# Real_Time_Clock.net
KiCad netlist of a schematic drawn in Altium Designer
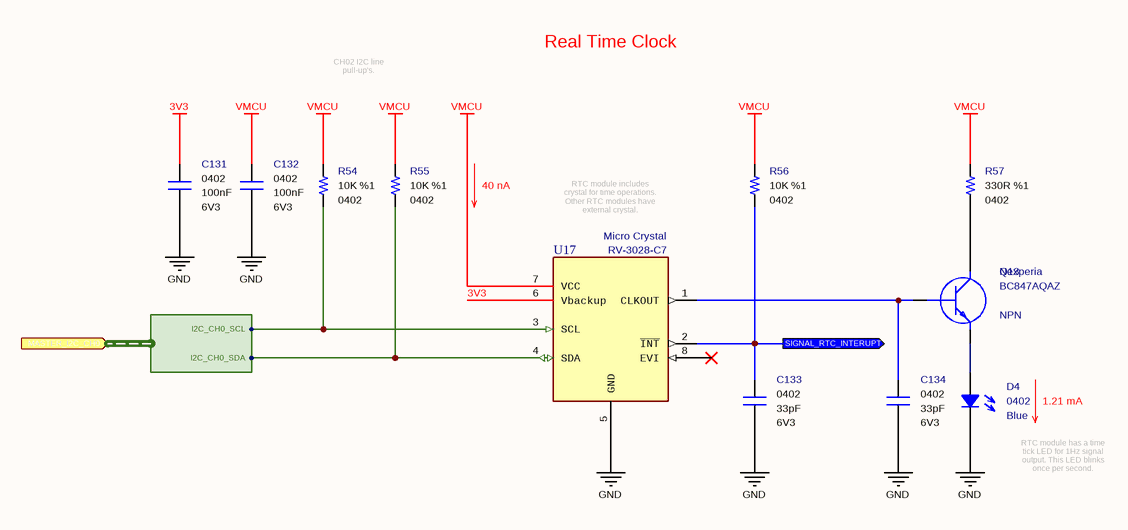
[diagram p0: Real Time Clock.SchDoc]

(export (version "E")
  (design (tool "Eeschema 10.0.6"))
  (components
    (comp (ref "C131")
      (value "100nF")
      (footprint "CAPACITOR_0402")
      (description "Capacitor - 100nF [0402-6V3] (Ceramic)")
      (fields
        (field (name "TOLERANCE") "%10")
        (field (name "CASE") "0402")
        (field (name "VOLTAGE") "6V3")
        (field (name "MANUFACTURER PART NUMBER") "04026D104KAT4A")
      )
      (libsource (lib "Ovoo_Library") (part "Capacitor - 100nF [0402-6V3]"))
    )
    (comp (ref "C132")
      (value "100nF")
      (footprint "CAPACITOR_0402")
      (description "Capacitor - 100nF [0402-6V3] (Ceramic)")
      (fields
        (field (name "TOLERANCE") "%10")
        (field (name "CASE") "0402")
        (field (name "VOLTAGE") "6V3")
        (field (name "MANUFACTURER PART NUMBER") "04026D104KAT4A")
      )
      (libsource (lib "Ovoo_Library") (part "Capacitor - 100nF [0402-6V3]"))
    )
    (comp (ref "C133")
      (value "33pF")
      (footprint "CAPACITOR_0402")
      (description "Capacitor - 33pF [0402] (Ceramic)")
      (fields
        (field (name "CASE") "0402")
        (field (name "TOLERANCE") "10%")
        (field (name "VOLTAGE") "6V3")
        (field (name "MANUFACTURER PART NUMBER") "C0402C330J9RACAUTO")
      )
      (libsource (lib "Ovoo_Library") (part "Capacitor - 33pF [0402-6V3]"))
    )
    (comp (ref "C134")
      (value "33pF")
      (footprint "CAPACITOR_0402")
      (description "Capacitor - 33pF [0402] (Ceramic)")
      (fields
        (field (name "CASE") "0402")
        (field (name "TOLERANCE") "10%")
        (field (name "VOLTAGE") "6V3")
        (field (name "MANUFACTURER PART NUMBER") "C0402C330J9RACAUTO")
      )
      (libsource (lib "Ovoo_Library") (part "Capacitor - 33pF [0402-6V3]"))
    )
    (comp (ref "D4")
      (value "SMD LED (Blue)")
      (footprint "LED_0402")
      (description "Standard LEDs - SMD PICOLEDTM;BLUE LED; 25M @ 5MA")
      (fields
        (field (name "CASE") "0402")
        (field (name "COLOR") "Blue")
        (field (name "MANUFACTURER PART NUMBER") "SMLP13BC8TT86")
        (field (name "MOUSER PART NUMBER") "755-SMLP13BC8TT86")
      )
      (libsource (lib "Ovoo_Library") (part "Diode - LED (0402-Blue)"))
    )
    (comp (ref "Q13")
      (value "Bipolar NPN Transistors")
      (footprint "SOT1215")
      (description "Bipolar Transistors - BJT BC847AQA/DFN1010D-3/REEL 7\" Q2")
      (fields
        (field (name "POLARITY") "NPN")
        (field (name "MOUSER PART NUMBER") "771-BC847AQAZ")
        (field (name "MANUFACTURER NAME") "Nexperia")
        (field (name "MANUFACTURER PART NUMBER") "BC847AQAZ")
      )
      (libsource (lib "Ovoo_Library") (part "Transistor - BC847"))
    )
    (comp (ref "R54")
      (value "10K")
      (footprint "RESISTOR_0402")
      (description "Thick Film Resistors - SMD 1/16 W 10 Kohms 1%")
      (fields
        (field (name "TOLERANCE") "%1")
        (field (name "CASE") "0402")
        (field (name "MANUFACTURER PART NUMBER") "CRCW040210K0FKED")
        (field (name "MOUSER PART NUMBER") "71-CRCW0402-10K-E3")
      )
      (libsource (lib "Ovoo_Library") (part "Resistor - 10K"))
    )
    (comp (ref "R55")
      (value "10K")
      (footprint "RESISTOR_0402")
      (description "Thick Film Resistors - SMD 1/16 W 10 Kohms 1%")
      (fields
        (field (name "TOLERANCE") "%1")
        (field (name "CASE") "0402")
        (field (name "MANUFACTURER PART NUMBER") "CRCW040210K0FKED")
        (field (name "MOUSER PART NUMBER") "71-CRCW0402-10K-E3")
      )
      (libsource (lib "Ovoo_Library") (part "Resistor - 10K"))
    )
    (comp (ref "R56")
      (value "10K")
      (footprint "RESISTOR_0402")
      (description "Thick Film Resistors - SMD 1/16 W 10 Kohms 1%")
      (fields
        (field (name "TOLERANCE") "%1")
        (field (name "CASE") "0402")
        (field (name "MANUFACTURER PART NUMBER") "CRCW040210K0FKED")
        (field (name "MOUSER PART NUMBER") "71-CRCW0402-10K-E3")
      )
      (libsource (lib "Ovoo_Library") (part "Resistor - 10K"))
    )
    (comp (ref "R57")
      (value "330R")
      (footprint "RESISTOR_0402")
      (description "Thick Film Resistors - SMD 1/16 W 330 Ohm 1%")
      (fields
        (field (name "TOLERANCE") "%1")
        (field (name "CASE") "0402")
        (field (name "MANUFACTURER PART NUMBER") "CRCW0402330RFKED")
        (field (name "MOUSER PART NUMBER") "71-CRCW0402-330-E3")
      )
      (libsource (lib "Ovoo_Library") (part "Resistor - 330R"))
    )
    (comp (ref "U17")
      (value "Real Time Clock")
      (footprint "RV-3028-C7")
      (description "Real Time Clock 32.768kHz I2C Time Acc. 1ppm")
      (fields
        (field (name "MOUSER PART NUMBER") "428-203591-MG01")
        (field (name "MANUFACTURER PART NUMBER") "RV-3028-C7")
        (field (name "MANUFACTURER NAME") "Micro Crystal")
      )
      (libsource (lib "Ovoo_Library") (part "IC - RV-3028-C7"))
    )
  )
  (nets
    (net (code "2") (name "/SIGNAL_RTC_INTERUPT") (class "Default")
      (node (ref "C133") (pin "1") (pinfunction "1_1") (pintype "passive"))
      (node (ref "R56") (pin "1") (pinfunction "1_1") (pintype "passive"))
      (node (ref "U17") (pin "2") (pinfunction "~{INT}_2") (pintype "output"))
    )
    (net (code "4") (name "3V3") (class "Default")
      (node (ref "C131") (pin "2") (pinfunction "2_2") (pintype "passive"))
      (node (ref "U17") (pin "6") (pinfunction "Vbackup_6") (pintype "power_in"))
    )
    (net (code "5") (name "GND") (class "Default")
      (node (ref "C131") (pin "1") (pinfunction "1_1") (pintype "passive"))
      (node (ref "C132") (pin "1") (pinfunction "1_1") (pintype "passive"))
      (node (ref "C133") (pin "2") (pinfunction "2_2") (pintype "passive"))
      (node (ref "C134") (pin "2") (pinfunction "2_2") (pintype "passive"))
      (node (ref "D4") (pin "1") (pinfunction "1_1") (pintype "passive"))
      (node (ref "U17") (pin "5") (pinfunction "GND_5") (pintype "power_in"))
    )
    (net (code "6") (name "Net-(Q13-B)") (class "Default")
      (node (ref "C134") (pin "1") (pinfunction "1_1") (pintype "passive"))
      (node (ref "Q13") (pin "1") (pinfunction "B_1") (pintype "passive"))
      (node (ref "U17") (pin "1") (pinfunction "CLKOUT_1") (pintype "output"))
    )
    (net (code "7") (name "Net-(Q13-C)") (class "Default")
      (node (ref "Q13") (pin "3") (pinfunction "C_3") (pintype "passive"))
      (node (ref "R57") (pin "1") (pinfunction "1_1") (pintype "passive"))
    )
    (net (code "8") (name "Net-(Q13-E)") (class "Default")
      (node (ref "D4") (pin "2") (pinfunction "2_2") (pintype "passive"))
      (node (ref "Q13") (pin "2") (pinfunction "E_2") (pintype "passive"))
    )
    (net (code "9") (name "Net-(U17-SCL)") (class "Default")
      (node (ref "R54") (pin "1") (pinfunction "1_1") (pintype "passive"))
      (node (ref "U17") (pin "3") (pinfunction "SCL_3") (pintype "input"))
    )
    (net (code "10") (name "Net-(U17-SDA)") (class "Default")
      (node (ref "R55") (pin "1") (pinfunction "1_1") (pintype "passive"))
      (node (ref "U17") (pin "4") (pinfunction "SDA_4") (pintype "bidirectional"))
    )
    (net (code "11") (name "VMCU") (class "Default")
      (node (ref "C132") (pin "2") (pinfunction "2_2") (pintype "passive"))
      (node (ref "R54") (pin "2") (pinfunction "2_2") (pintype "passive"))
      (node (ref "R55") (pin "2") (pinfunction "2_2") (pintype "passive"))
      (node (ref "R56") (pin "2") (pinfunction "2_2") (pintype "passive"))
      (node (ref "R57") (pin "2") (pinfunction "2_2") (pintype "passive"))
      (node (ref "U17") (pin "7") (pinfunction "VCC_7") (pintype "power_in"))
    )
    (net (code "12") (name "unconnected-(U17-EVI-Pad8)") (class "Default")
      (node (ref "U17") (pin "8") (pinfunction "EVI_8") (pintype "input+no_connect"))
    )
  )
)
